# tinyduino-breakout-mk-4_2.net
KiCad netlist of a schematic drawn in EAGLE
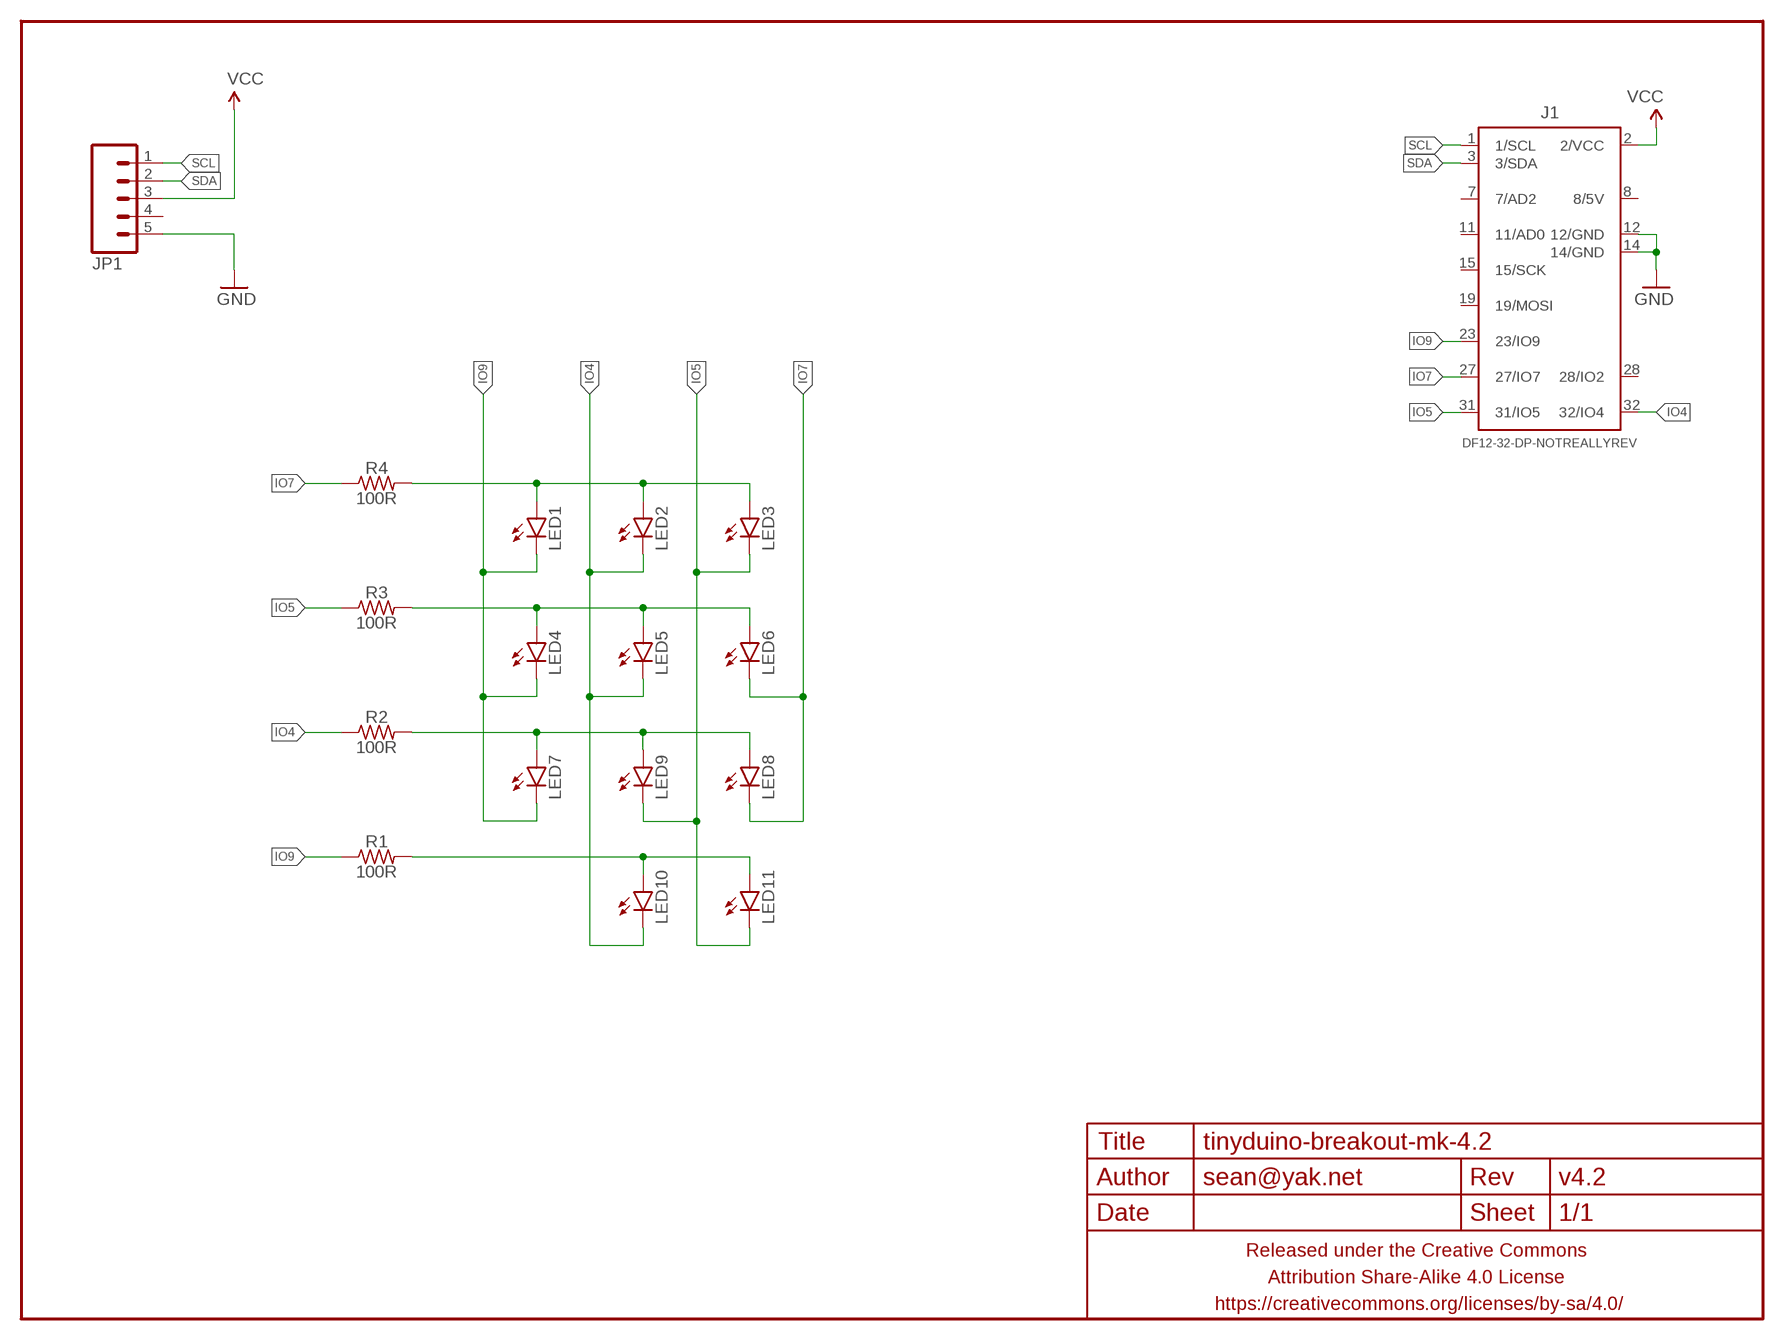
[diagram p0: schematic, sheet 1]

(export (version "E")
  (design (tool "Eeschema 10.0.6"))
  (components
    (comp (ref "FRAME1")
      (value "FRAME-LETTERNO_PACKAGE")
      (footprint "eagle-import:DUMMY")
      (fields (field (name "DESIGNER") "sean@yak.net") (field (name "VERSION") "v4.2"))
      (libsource (lib "eagle-import") (part "FRAME-LETTERNO_PACKAGE"))
    )
    (comp (ref "J1")
      (value "DF12-32-DP-NOTREALLYREV")
      (footprint "eagle-import:DF12-32-DP-I2C+EXTRA-REV")
      (libsource (lib "eagle-import") (part "DF12-32-DP-NOTREALLYREV"))
    )
    (comp (ref "JP1")
      (value "M05SMD-SHORT")
      (footprint "eagle-import:1X05-SMD-SHORT")
      (libsource (lib "eagle-import") (part "M05SMD-SHORT"))
    )
    (comp (ref "LED1")
      (value "LED0603")
      (footprint "eagle-import:LED-0603")
      (libsource (lib "eagle-import") (part "LED0603"))
    )
    (comp (ref "LED2")
      (value "LED0603")
      (footprint "eagle-import:LED-0603")
      (libsource (lib "eagle-import") (part "LED0603"))
    )
    (comp (ref "LED3")
      (value "LED0603")
      (footprint "eagle-import:LED-0603")
      (libsource (lib "eagle-import") (part "LED0603"))
    )
    (comp (ref "LED4")
      (value "LED0603")
      (footprint "eagle-import:LED-0603")
      (libsource (lib "eagle-import") (part "LED0603"))
    )
    (comp (ref "LED5")
      (value "LED0603")
      (footprint "eagle-import:LED-0603")
      (libsource (lib "eagle-import") (part "LED0603"))
    )
    (comp (ref "LED6")
      (value "LED0603")
      (footprint "eagle-import:LED-0603")
      (libsource (lib "eagle-import") (part "LED0603"))
    )
    (comp (ref "LED7")
      (value "LED0603")
      (footprint "eagle-import:LED-0603")
      (libsource (lib "eagle-import") (part "LED0603"))
    )
    (comp (ref "LED8")
      (value "LED0603")
      (footprint "eagle-import:LED-0603")
      (libsource (lib "eagle-import") (part "LED0603"))
    )
    (comp (ref "LED9")
      (value "LED0603")
      (footprint "eagle-import:LED-0603")
      (libsource (lib "eagle-import") (part "LED0603"))
    )
    (comp (ref "LED10")
      (value "LED0603")
      (footprint "eagle-import:LED-0603")
      (libsource (lib "eagle-import") (part "LED0603"))
    )
    (comp (ref "LED11")
      (value "LED0603")
      (footprint "eagle-import:LED-0603")
      (libsource (lib "eagle-import") (part "LED0603"))
    )
    (comp (ref "R1")
      (value "100R")
      (footprint "eagle-import:R0603")
      (libsource (lib "eagle-import") (part "RESISTORR0603"))
    )
    (comp (ref "R2")
      (value "100R")
      (footprint "eagle-import:R0603")
      (libsource (lib "eagle-import") (part "RESISTORR0603"))
    )
    (comp (ref "R3")
      (value "100R")
      (footprint "eagle-import:R0603")
      (libsource (lib "eagle-import") (part "RESISTORR0603"))
    )
    (comp (ref "R4")
      (value "100R")
      (footprint "eagle-import:R0603")
      (libsource (lib "eagle-import") (part "RESISTORR0603"))
    )
  )
  (nets
    (net (code "1") (name "GND") (class "Default")
      (node (ref "J1") (pin "12") (pinfunction "12/GND_12") (pintype "bidirectional"))
      (node (ref "J1") (pin "14") (pinfunction "14/GND_14") (pintype "bidirectional"))
      (node (ref "JP1") (pin "5") (pinfunction "5_5") (pintype "passive"))
    )
    (net (code "2") (name "IO4") (class "Default")
      (node (ref "J1") (pin "32") (pinfunction "32/IO4_32") (pintype "bidirectional"))
      (node (ref "LED10") (pin "C") (pinfunction "C_C") (pintype "passive"))
      (node (ref "LED2") (pin "C") (pinfunction "C_C") (pintype "passive"))
      (node (ref "LED5") (pin "C") (pinfunction "C_C") (pintype "passive"))
      (node (ref "R2") (pin "1") (pinfunction "1_1") (pintype "passive"))
    )
    (net (code "3") (name "IO5") (class "Default")
      (node (ref "J1") (pin "31") (pinfunction "31/IO5_31") (pintype "bidirectional"))
      (node (ref "LED11") (pin "C") (pinfunction "C_C") (pintype "passive"))
      (node (ref "LED3") (pin "C") (pinfunction "C_C") (pintype "passive"))
      (node (ref "LED9") (pin "C") (pinfunction "C_C") (pintype "passive"))
      (node (ref "R3") (pin "1") (pinfunction "1_1") (pintype "passive"))
    )
    (net (code "4") (name "IO7") (class "Default")
      (node (ref "J1") (pin "27") (pinfunction "27/IO7_27") (pintype "bidirectional"))
      (node (ref "LED6") (pin "C") (pinfunction "C_C") (pintype "passive"))
      (node (ref "LED8") (pin "C") (pinfunction "C_C") (pintype "passive"))
      (node (ref "R4") (pin "1") (pinfunction "1_1") (pintype "passive"))
    )
    (net (code "5") (name "IO9") (class "Default")
      (node (ref "J1") (pin "23") (pinfunction "23/IO9_23") (pintype "bidirectional"))
      (node (ref "LED1") (pin "C") (pinfunction "C_C") (pintype "passive"))
      (node (ref "LED4") (pin "C") (pinfunction "C_C") (pintype "passive"))
      (node (ref "LED7") (pin "C") (pinfunction "C_C") (pintype "passive"))
      (node (ref "R1") (pin "1") (pinfunction "1_1") (pintype "passive"))
    )
    (net (code "6") (name "Net-(LED1-PadA)") (class "Default")
      (node (ref "LED1") (pin "A") (pinfunction "A_A") (pintype "passive"))
      (node (ref "LED2") (pin "A") (pinfunction "A_A") (pintype "passive"))
      (node (ref "LED3") (pin "A") (pinfunction "A_A") (pintype "passive"))
      (node (ref "R4") (pin "2") (pinfunction "2_2") (pintype "passive"))
    )
    (net (code "7") (name "Net-(LED4-PadA)") (class "Default")
      (node (ref "LED4") (pin "A") (pinfunction "A_A") (pintype "passive"))
      (node (ref "LED5") (pin "A") (pinfunction "A_A") (pintype "passive"))
      (node (ref "LED6") (pin "A") (pinfunction "A_A") (pintype "passive"))
      (node (ref "R3") (pin "2") (pinfunction "2_2") (pintype "passive"))
    )
    (net (code "8") (name "Net-(LED7-PadA)") (class "Default")
      (node (ref "LED7") (pin "A") (pinfunction "A_A") (pintype "passive"))
      (node (ref "LED8") (pin "A") (pinfunction "A_A") (pintype "passive"))
      (node (ref "LED9") (pin "A") (pinfunction "A_A") (pintype "passive"))
      (node (ref "R2") (pin "2") (pinfunction "2_2") (pintype "passive"))
    )
    (net (code "9") (name "Net-(LED10-PadA)") (class "Default")
      (node (ref "LED10") (pin "A") (pinfunction "A_A") (pintype "passive"))
      (node (ref "LED11") (pin "A") (pinfunction "A_A") (pintype "passive"))
      (node (ref "R1") (pin "2") (pinfunction "2_2") (pintype "passive"))
    )
    (net (code "10") (name "SCL") (class "Default")
      (node (ref "J1") (pin "1") (pinfunction "1/SCL_1") (pintype "bidirectional"))
      (node (ref "JP1") (pin "1") (pinfunction "1_1") (pintype "passive"))
    )
    (net (code "11") (name "SDA") (class "Default")
      (node (ref "J1") (pin "3") (pinfunction "3/SDA_3") (pintype "bidirectional"))
      (node (ref "JP1") (pin "2") (pinfunction "2_2") (pintype "passive"))
    )
    (net (code "12") (name "VCC") (class "Default")
      (node (ref "J1") (pin "2") (pinfunction "2/VCC_2") (pintype "bidirectional"))
      (node (ref "JP1") (pin "3") (pinfunction "3_3") (pintype "passive"))
    )
    (net (code "13") (name "unconnected-(J1-7{slash}AD2-Pad7)") (class "Default")
      (node (ref "J1") (pin "7") (pinfunction "7/AD2_7") (pintype "bidirectional"))
    )
    (net (code "14") (name "unconnected-(J1-8{slash}5V-Pad8)") (class "Default")
      (node (ref "J1") (pin "8") (pinfunction "8/5V_8") (pintype "bidirectional"))
    )
    (net (code "15") (name "unconnected-(J1-11{slash}AD0-Pad11)") (class "Default")
      (node (ref "J1") (pin "11") (pinfunction "11/AD0_11") (pintype "bidirectional"))
    )
    (net (code "16") (name "unconnected-(J1-15{slash}SCK-Pad15)") (class "Default")
      (node (ref "J1") (pin "15") (pinfunction "15/SCK_15") (pintype "bidirectional"))
    )
    (net (code "17") (name "unconnected-(J1-19{slash}MOSI-Pad19)") (class "Default")
      (node (ref "J1") (pin "19") (pinfunction "19/MOSI_19") (pintype "bidirectional"))
    )
    (net (code "18") (name "unconnected-(J1-28{slash}IO2-Pad28)") (class "Default")
      (node (ref "J1") (pin "28") (pinfunction "28/IO2_28") (pintype "bidirectional"))
    )
    (net (code "19") (name "unconnected-(JP1-Pad4)") (class "Default")
      (node (ref "JP1") (pin "4") (pinfunction "4_4") (pintype "passive"))
    )
  )
)
